# ManInTheMiddleCable.net
KiCad netlist of a schematic drawn in Altium Designer
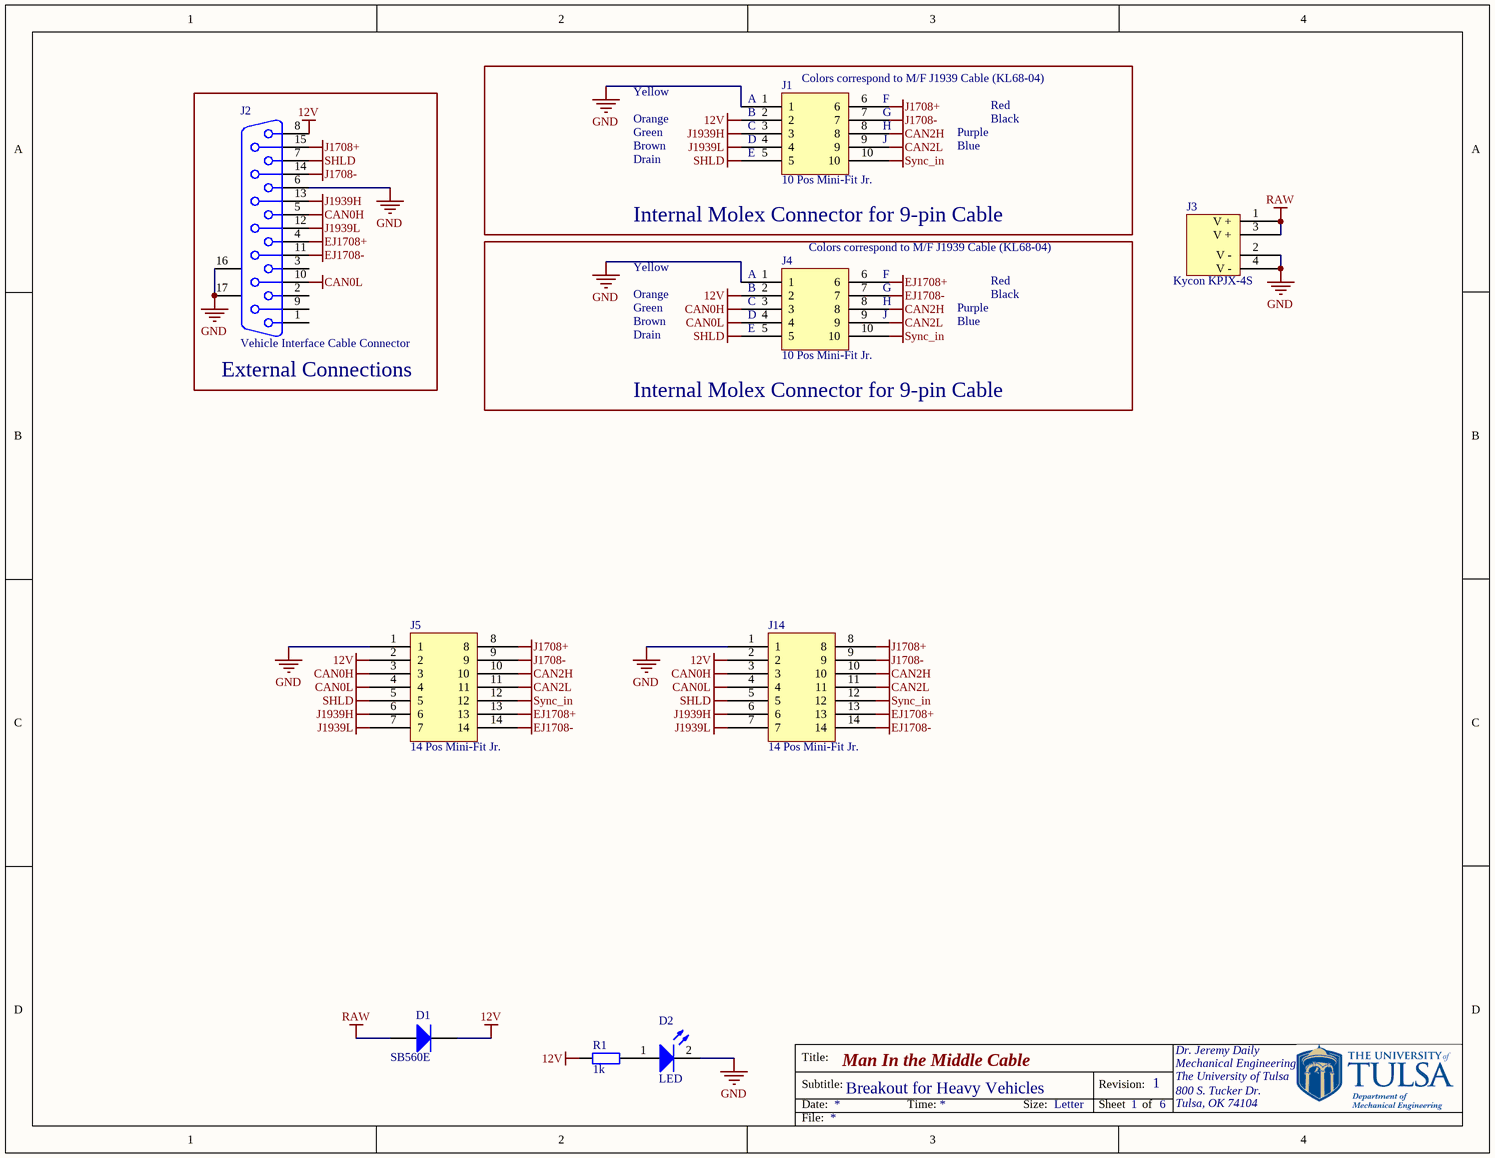
[diagram p0: ManInTheMiddleCable.SchDoc]

(export (version "E")
  (design (tool "Eeschema 10.0.6"))
  (components
    (comp (ref "D1")
      (value "SB560E")
      (footprint "DO-201AD")
      (description "Schottky Diodes & Rectifiers 2.0 Amp 150 Volt")
      (fields (field (name "MANUFACTURER") "STMicroelectronics") (field (name "PARTNUMBER") "STPS2150"))
      (libsource (lib "Miscellaneous Devices") (part "Diode 1N4003"))
    )
    (comp (ref "D2")
      (value "LED")
      (footprint "LED - 5mm Through Hole")
      (description "LED COOL WHITE CLR 4.8MM RND T/H")
      (fields (field (name "MANUFACTURER") "Cree Inc.") (field (name "PARTNUMBER") "C535A-WJN-CT0W0231"))
      (libsource (lib "Custom Parts Library") (part "SMT LED"))
    )
    (comp (ref "J1")
      (value "10 Pos Mini-Fit Jr.")
      (footprint "10 pos Mini-Fit Jr. R/A Header")
      (description "10 Positions Header - Shrouded Connector 0.165in (4.20mm) Through Hole - Right Angle Gold")
      (fields (field (name "MANUFACTURER") "Molex") (field (name "PARTNUMBER") "39-30-1102"))
      (libsource (lib "Molex Mini-Fit Jr") (part "10 Pos Header"))
    )
    (comp (ref "J2")
      (value "Vehicle Interface Cable Connector")
      (footprint "DSUB1.385-2H15")
      (description "Receptacle Assembly, 15 Position, Right Angle")
      (fields (field (name "MANUFACTURER") "Amphenol FCI") (field (name "PARTNUMBER") "D15S33E4GV00LF"))
      (libsource (lib "Miscellaneous Connectors") (part "D Connector 15"))
    )
    (comp (ref "J3")
      (value "Kycon KPJX-4S")
      (footprint "KPJX-4S-S")
      (description "DC Power Connectors 4P JACK SKT SHIELDED SNAP AND LOCK")
      (fields (field (name "MANUFACTURER") "Kycon") (field (name "PARTNUMBER") "KPJX-4S-S"))
      (libsource (lib "SSS Integrated Library") (part "Power Entry Jack - 4 Pin"))
    )
    (comp (ref "J4")
      (value "10 Pos Mini-Fit Jr.")
      (footprint "10 pos Mini-Fit Jr. R/A Header")
      (description "10 Positions Header - Shrouded Connector 0.165in (4.20mm) Through Hole - Right Angle Gold")
      (fields (field (name "MANUFACTURER") "Molex") (field (name "PARTNUMBER") "39-30-1102"))
      (libsource (lib "Molex Mini-Fit Jr") (part "10 Pos Header"))
    )
    (comp (ref "J5")
      (value "14 Pos Mini-Fit Jr.")
      (footprint "14 pos Mini-Fit Jr. R/A Header")
      (fields (field (name "MANUFACTURER") "Molex") (field (name "PARTNUMBER") "39-30-1140"))
      (libsource (lib "Molex Mini-Fit Jr") (part "14 Pos Header"))
    )
    (comp (ref "J14")
      (value "14 Pos Mini-Fit Jr.")
      (footprint "14 pos Mini-Fit Jr. R/A Header")
      (fields (field (name "MANUFACTURER") "Molex") (field (name "PARTNUMBER") "39-30-1140"))
      (libsource (lib "Molex Mini-Fit Jr") (part "14 Pos Header"))
    )
    (comp (ref "R1")
      (value "1k")
      (footprint "AXIAL-0.4")
      (description "RES 330 OHM 1/4W 1% AXIAL")
      (fields
        (field (name "MANUFACTURER") "Stackpole Electronics Inc.")
        (field (name "PARTNUMBER") "RNMF14FTC330R")
      )
      (libsource (lib "Miscellaneous Devices") (part "Res2"))
    )
  )
  (nets
    (net (code "1") (name "12V") (class "Default")
      (node (ref "D1") (pin "2") (pinfunction "K_2") (pintype "passive"))
      (node (ref "J1") (pin "2") (pinfunction "2_2") (pintype "passive"))
      (node (ref "J14") (pin "2") (pinfunction "2_2") (pintype "passive"))
      (node (ref "J2") (pin "8") (pinfunction "8_8") (pintype "passive"))
      (node (ref "J4") (pin "2") (pinfunction "2_2") (pintype "passive"))
      (node (ref "J5") (pin "2") (pinfunction "2_2") (pintype "passive"))
      (node (ref "R1") (pin "1") (pinfunction "1_1") (pintype "passive"))
    )
    (net (code "2") (name "CAN0H") (class "Default")
      (node (ref "J14") (pin "3") (pinfunction "3_3") (pintype "passive"))
      (node (ref "J2") (pin "5") (pinfunction "5_5") (pintype "passive"))
      (node (ref "J4") (pin "3") (pinfunction "3_3") (pintype "passive"))
      (node (ref "J5") (pin "3") (pinfunction "3_3") (pintype "passive"))
    )
    (net (code "3") (name "CAN0L") (class "Default")
      (node (ref "J14") (pin "4") (pinfunction "4_4") (pintype "passive"))
      (node (ref "J2") (pin "10") (pinfunction "10_10") (pintype "passive"))
      (node (ref "J4") (pin "4") (pinfunction "4_4") (pintype "passive"))
      (node (ref "J5") (pin "4") (pinfunction "4_4") (pintype "passive"))
    )
    (net (code "4") (name "CAN2H") (class "Default")
      (node (ref "J1") (pin "8") (pinfunction "8_8") (pintype "passive"))
      (node (ref "J14") (pin "10") (pinfunction "10_10") (pintype "passive"))
      (node (ref "J4") (pin "8") (pinfunction "8_8") (pintype "passive"))
      (node (ref "J5") (pin "10") (pinfunction "10_10") (pintype "passive"))
    )
    (net (code "5") (name "CAN2L") (class "Default")
      (node (ref "J1") (pin "9") (pinfunction "9_9") (pintype "passive"))
      (node (ref "J14") (pin "11") (pinfunction "11_11") (pintype "passive"))
      (node (ref "J4") (pin "9") (pinfunction "9_9") (pintype "passive"))
      (node (ref "J5") (pin "11") (pinfunction "11_11") (pintype "passive"))
    )
    (net (code "6") (name "EJ1708+") (class "Default")
      (node (ref "J14") (pin "13") (pinfunction "13_13") (pintype "passive"))
      (node (ref "J2") (pin "4") (pinfunction "4_4") (pintype "passive"))
      (node (ref "J4") (pin "6") (pinfunction "6_6") (pintype "passive"))
      (node (ref "J5") (pin "13") (pinfunction "13_13") (pintype "passive"))
    )
    (net (code "7") (name "EJ1708-") (class "Default")
      (node (ref "J14") (pin "14") (pinfunction "14_14") (pintype "passive"))
      (node (ref "J2") (pin "11") (pinfunction "11_11") (pintype "passive"))
      (node (ref "J4") (pin "7") (pinfunction "7_7") (pintype "passive"))
      (node (ref "J5") (pin "14") (pinfunction "14_14") (pintype "passive"))
    )
    (net (code "8") (name "GND") (class "Default")
      (node (ref "D2") (pin "2") (pinfunction "K_2") (pintype "passive"))
      (node (ref "J1") (pin "1") (pinfunction "1_1") (pintype "passive"))
      (node (ref "J14") (pin "1") (pinfunction "1_1") (pintype "passive"))
      (node (ref "J2") (pin "16") (pinfunction "MH1_16") (pintype "passive"))
      (node (ref "J2") (pin "17") (pinfunction "MH2_17") (pintype "passive"))
      (node (ref "J2") (pin "6") (pinfunction "6_6") (pintype "passive"))
      (node (ref "J3") (pin "2") (pinfunction "V_-_2") (pintype "passive"))
      (node (ref "J3") (pin "4") (pinfunction "V_-_4") (pintype "passive"))
      (node (ref "J4") (pin "1") (pinfunction "1_1") (pintype "passive"))
      (node (ref "J5") (pin "1") (pinfunction "1_1") (pintype "passive"))
    )
    (net (code "9") (name "J1708+") (class "Default")
      (node (ref "J1") (pin "6") (pinfunction "6_6") (pintype "passive"))
      (node (ref "J14") (pin "8") (pinfunction "8_8") (pintype "passive"))
      (node (ref "J2") (pin "15") (pinfunction "15_15") (pintype "passive"))
      (node (ref "J5") (pin "8") (pinfunction "8_8") (pintype "passive"))
    )
    (net (code "10") (name "J1708-") (class "Default")
      (node (ref "J1") (pin "7") (pinfunction "7_7") (pintype "passive"))
      (node (ref "J14") (pin "9") (pinfunction "9_9") (pintype "passive"))
      (node (ref "J2") (pin "14") (pinfunction "14_14") (pintype "passive"))
      (node (ref "J5") (pin "9") (pinfunction "9_9") (pintype "passive"))
    )
    (net (code "11") (name "J1939H") (class "Default")
      (node (ref "J1") (pin "3") (pinfunction "3_3") (pintype "passive"))
      (node (ref "J14") (pin "6") (pinfunction "6_6") (pintype "passive"))
      (node (ref "J2") (pin "13") (pinfunction "13_13") (pintype "passive"))
      (node (ref "J5") (pin "6") (pinfunction "6_6") (pintype "passive"))
    )
    (net (code "12") (name "J1939L") (class "Default")
      (node (ref "J1") (pin "4") (pinfunction "4_4") (pintype "passive"))
      (node (ref "J14") (pin "7") (pinfunction "7_7") (pintype "passive"))
      (node (ref "J2") (pin "12") (pinfunction "12_12") (pintype "passive"))
      (node (ref "J5") (pin "7") (pinfunction "7_7") (pintype "passive"))
    )
    (net (code "13") (name "Net-(D2-A)") (class "Default")
      (node (ref "D2") (pin "1") (pinfunction "A_1") (pintype "passive"))
      (node (ref "R1") (pin "2") (pinfunction "2_2") (pintype "passive"))
    )
    (net (code "14") (name "RAW") (class "Default")
      (node (ref "D1") (pin "1") (pinfunction "A_1") (pintype "passive"))
      (node (ref "J3") (pin "1") (pinfunction "V_+_1") (pintype "passive"))
      (node (ref "J3") (pin "3") (pinfunction "V_+_3") (pintype "passive"))
    )
    (net (code "15") (name "SHLD") (class "Default")
      (node (ref "J1") (pin "5") (pinfunction "5_5") (pintype "passive"))
      (node (ref "J14") (pin "5") (pinfunction "5_5") (pintype "passive"))
      (node (ref "J2") (pin "7") (pinfunction "7_7") (pintype "passive"))
      (node (ref "J4") (pin "5") (pinfunction "5_5") (pintype "passive"))
      (node (ref "J5") (pin "5") (pinfunction "5_5") (pintype "passive"))
    )
    (net (code "16") (name "Sync_in") (class "Default")
      (node (ref "J1") (pin "10") (pinfunction "10_10") (pintype "passive"))
      (node (ref "J14") (pin "12") (pinfunction "12_12") (pintype "passive"))
      (node (ref "J4") (pin "10") (pinfunction "10_10") (pintype "passive"))
      (node (ref "J5") (pin "12") (pinfunction "12_12") (pintype "passive"))
    )
    (net (code "17") (name "unconnected-(J2-Pad1)") (class "Default")
      (node (ref "J2") (pin "1") (pinfunction "1_1") (pintype "passive"))
    )
    (net (code "18") (name "unconnected-(J2-Pad2)") (class "Default")
      (node (ref "J2") (pin "2") (pinfunction "2_2") (pintype "passive"))
    )
    (net (code "19") (name "unconnected-(J2-Pad3)") (class "Default")
      (node (ref "J2") (pin "3") (pinfunction "3_3") (pintype "passive"))
    )
    (net (code "20") (name "unconnected-(J2-Pad9)") (class "Default")
      (node (ref "J2") (pin "9") (pinfunction "9_9") (pintype "passive"))
    )
  )
)
